# idro900ma.net
KiCad netlist of a schematic drawn in Altium Designer
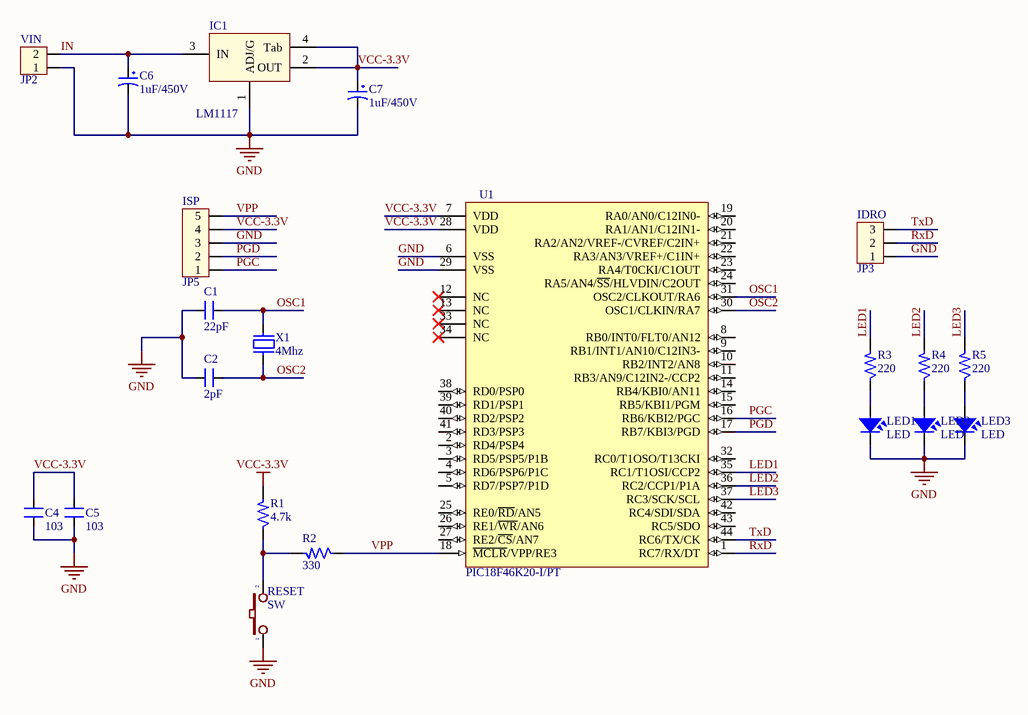
[diagram p0: idro900ma.SchDoc]

(export (version "E")
  (design (tool "Eeschema 10.0.6"))
  (components
    (comp (ref "C1")
      (value "22pF")
      (footprint "SM-0805")
      (description "Cap SMD")
      (libsource (lib "syhaunguyen") (part "CM"))
    )
    (comp (ref "C2")
      (value "2pF")
      (footprint "SM-0805")
      (description "Cap SMD")
      (libsource (lib "syhaunguyen") (part "CM"))
    )
    (comp (ref "C4")
      (value "103")
      (footprint "SM-0805")
      (description "Cap SMD")
      (libsource (lib "syhaunguyen") (part "CM"))
    )
    (comp (ref "C5")
      (value "103")
      (footprint "SM-0805")
      (description "Cap SMD")
      (libsource (lib "syhaunguyen") (part "CM"))
    )
    (comp (ref "C6")
      (value "1uF/450V")
      (footprint "SM-0805")
      (description "Cap 4700uF/50V")
      (libsource (lib "syhaunguyen") (part "CP8"))
    )
    (comp (ref "C7")
      (value "1uF/450V")
      (footprint "SM-0805")
      (description "Cap 4700uF/50V")
      (libsource (lib "syhaunguyen") (part "CP8"))
    )
    (comp (ref "IC1")
      (value "LM1117")
      (footprint "SOT223-4N")
      (description "3v3")
      (libsource (lib "syhaunguyen") (part "LM1117"))
    )
    (comp (ref "IDRO")
      (value "JP3")
      (footprint "CON3")
      (description "Connector 3")
      (libsource (lib "syhaunguyen") (part "Con3"))
    )
    (comp (ref "ISP")
      (value "JP5")
      (footprint "CON5")
      (description "Connector 5")
      (libsource (lib "syhaunguyen") (part "Con5"))
    )
    (comp (ref "LED1")
      (value "LED")
      (footprint "LED-5 GRe")
      (description "LED Single colour Green and Red")
      (libsource (lib "syhaunguyen") (part "LED"))
    )
    (comp (ref "LED2")
      (value "LED")
      (footprint "LED-5 GRe")
      (description "LED Single colour Green and Red")
      (libsource (lib "syhaunguyen") (part "LED"))
    )
    (comp (ref "LED3")
      (value "LED")
      (footprint "LED-5 GRe")
      (description "LED Single colour Green and Red")
      (libsource (lib "syhaunguyen") (part "LED"))
    )
    (comp (ref "R1")
      (value "4.7k")
      (footprint "SM-0805")
      (description "Resistor 1/4W")
      (libsource (lib "syhaunguyen") (part "R"))
    )
    (comp (ref "R2")
      (value "330")
      (footprint "SM-0805")
      (description "Resistor 1/4W")
      (libsource (lib "syhaunguyen") (part "R"))
    )
    (comp (ref "R3")
      (value "220")
      (footprint "SM-0805")
      (description "Resistor 1/4W")
      (libsource (lib "syhaunguyen") (part "R"))
    )
    (comp (ref "R4")
      (value "220")
      (footprint "SM-0805")
      (description "Resistor 1/4W")
      (libsource (lib "syhaunguyen") (part "R"))
    )
    (comp (ref "R5")
      (value "220")
      (footprint "SM-0805")
      (description "Resistor 1/4W")
      (libsource (lib "syhaunguyen") (part "R"))
    )
    (comp (ref "RESET")
      (value "SW")
      (footprint "SW2")
      (description "Switch button 2 pin")
      (libsource (lib "syhaunguyen") (part "SW2"))
    )
    (comp (ref "U1")
      (value "PIC18F46K20-I/PT")
      (footprint "TQFP-PT44_N")
      (fields (field (name "PUBLISHER") "Altium Limited"))
      (libsource (lib "Microchip Microcontroller 8-Bit PIC18") (part "PIC18F46K20-I/PT"))
    )
    (comp (ref "VIN")
      (value "JP2")
      (footprint "CON2")
      (description "Connector 2")
      (libsource (lib "syhaunguyen") (part "Con2"))
    )
    (comp (ref "X1")
      (value "4Mhz")
      (footprint "XT2")
      (description "Crystal For all Crystal 2pin.")
      (libsource (lib "syhaunguyen") (part "XT2"))
    )
  )
  (nets
    (net (code "1") (name "/IN") (class "Default")
      (node (ref "C6") (pin "1") (pinfunction "1_1") (pintype "passive"))
      (node (ref "IC1") (pin "3") (pinfunction "IN_3") (pintype "passive"))
      (node (ref "VIN") (pin "2") (pinfunction "2_2") (pintype "passive"))
    )
    (net (code "2") (name "/LED1") (class "Default")
      (node (ref "R3") (pin "2") (pinfunction "2_2") (pintype "passive"))
      (node (ref "U1") (pin "35") (pinfunction "RC1/T1OSI/CCP2_35") (pintype "bidirectional"))
    )
    (net (code "3") (name "/LED2") (class "Default")
      (node (ref "R4") (pin "2") (pinfunction "2_2") (pintype "passive"))
      (node (ref "U1") (pin "36") (pinfunction "RC2/CCP1/P1A_36") (pintype "bidirectional"))
    )
    (net (code "4") (name "/LED3") (class "Default")
      (node (ref "R5") (pin "2") (pinfunction "2_2") (pintype "passive"))
      (node (ref "U1") (pin "37") (pinfunction "RC3/SCK/SCL_37") (pintype "bidirectional"))
    )
    (net (code "5") (name "/OSC1") (class "Default")
      (node (ref "C1") (pin "2") (pinfunction "2_2") (pintype "passive"))
      (node (ref "U1") (pin "31") (pinfunction "OSC2/CLKOUT/RA6_31") (pintype "bidirectional"))
      (node (ref "X1") (pin "2") (pinfunction "2_2") (pintype "passive"))
    )
    (net (code "6") (name "/OSC2") (class "Default")
      (node (ref "C2") (pin "2") (pinfunction "2_2") (pintype "passive"))
      (node (ref "U1") (pin "30") (pinfunction "OSC1/CLKIN/RA7_30") (pintype "bidirectional"))
      (node (ref "X1") (pin "1") (pinfunction "1_1") (pintype "passive"))
    )
    (net (code "7") (name "/PGC") (class "Default")
      (node (ref "ISP") (pin "1") (pinfunction "1_1") (pintype "passive"))
      (node (ref "U1") (pin "16") (pinfunction "RB6/KBI2/PGC_16") (pintype "bidirectional"))
    )
    (net (code "8") (name "/PGD") (class "Default")
      (node (ref "ISP") (pin "2") (pinfunction "2_2") (pintype "passive"))
      (node (ref "U1") (pin "17") (pinfunction "RB7/KBI3/PGD_17") (pintype "bidirectional"))
    )
    (net (code "9") (name "/RxD") (class "Default")
      (node (ref "IDRO") (pin "2") (pinfunction "2_2") (pintype "passive"))
      (node (ref "U1") (pin "1") (pinfunction "RC7/RX/DT_1") (pintype "bidirectional"))
    )
    (net (code "10") (name "/TxD") (class "Default")
      (node (ref "IDRO") (pin "3") (pinfunction "3_3") (pintype "passive"))
      (node (ref "U1") (pin "44") (pinfunction "RC6/TX/CK_44") (pintype "bidirectional"))
    )
    (net (code "11") (name "/VPP") (class "Default")
      (node (ref "ISP") (pin "5") (pinfunction "5_5") (pintype "passive"))
      (node (ref "R2") (pin "1") (pinfunction "1_1") (pintype "passive"))
      (node (ref "U1") (pin "18") (pinfunction "~{MCLR}/VPP/RE3_18") (pintype "input"))
    )
    (net (code "12") (name "GND") (class "Default")
      (node (ref "C1") (pin "1") (pinfunction "1_1") (pintype "passive"))
      (node (ref "C2") (pin "1") (pinfunction "1_1") (pintype "passive"))
      (node (ref "C4") (pin "1") (pinfunction "1_1") (pintype "passive"))
      (node (ref "C5") (pin "1") (pinfunction "1_1") (pintype "passive"))
      (node (ref "C6") (pin "2") (pinfunction "2_2") (pintype "passive"))
      (node (ref "C7") (pin "2") (pinfunction "2_2") (pintype "passive"))
      (node (ref "IC1") (pin "1") (pinfunction "ADJ/G_1") (pintype "passive"))
      (node (ref "IDRO") (pin "1") (pinfunction "1_1") (pintype "passive"))
      (node (ref "ISP") (pin "3") (pinfunction "3_3") (pintype "passive"))
      (node (ref "LED1") (pin "2") (pinfunction "2_2") (pintype "passive"))
      (node (ref "LED2") (pin "2") (pinfunction "2_2") (pintype "passive"))
      (node (ref "LED3") (pin "2") (pinfunction "2_2") (pintype "passive"))
      (node (ref "RESET") (pin "1") (pinfunction "1_1") (pintype "passive"))
      (node (ref "U1") (pin "29") (pinfunction "VSS_29") (pintype "power_in"))
      (node (ref "U1") (pin "6") (pinfunction "VSS_6") (pintype "power_in"))
      (node (ref "VIN") (pin "1") (pinfunction "1_1") (pintype "passive"))
    )
    (net (code "13") (name "Net-(LED1-Pad1)") (class "Default")
      (node (ref "LED1") (pin "1") (pinfunction "1_1") (pintype "passive"))
      (node (ref "R3") (pin "1") (pinfunction "1_1") (pintype "passive"))
    )
    (net (code "14") (name "Net-(LED2-Pad1)") (class "Default")
      (node (ref "LED2") (pin "1") (pinfunction "1_1") (pintype "passive"))
      (node (ref "R4") (pin "1") (pinfunction "1_1") (pintype "passive"))
    )
    (net (code "15") (name "Net-(LED3-Pad1)") (class "Default")
      (node (ref "LED3") (pin "1") (pinfunction "1_1") (pintype "passive"))
      (node (ref "R5") (pin "1") (pinfunction "1_1") (pintype "passive"))
    )
    (net (code "16") (name "Net-(R1-Pad1)") (class "Default")
      (node (ref "R1") (pin "1") (pinfunction "1_1") (pintype "passive"))
      (node (ref "R2") (pin "2") (pinfunction "2_2") (pintype "passive"))
      (node (ref "RESET") (pin "2") (pinfunction "2_2") (pintype "passive"))
    )
    (net (code "17") (name "VCC-3.3V") (class "Default")
      (node (ref "C4") (pin "2") (pinfunction "2_2") (pintype "passive"))
      (node (ref "C5") (pin "2") (pinfunction "2_2") (pintype "passive"))
      (node (ref "C7") (pin "1") (pinfunction "1_1") (pintype "passive"))
      (node (ref "IC1") (pin "2") (pinfunction "OUT_2") (pintype "passive"))
      (node (ref "IC1") (pin "4") (pinfunction "Tab_4") (pintype "passive"))
      (node (ref "ISP") (pin "4") (pinfunction "4_4") (pintype "passive"))
      (node (ref "R1") (pin "2") (pinfunction "2_2") (pintype "passive"))
      (node (ref "U1") (pin "28") (pinfunction "VDD_28") (pintype "power_in"))
      (node (ref "U1") (pin "7") (pinfunction "VDD_7") (pintype "power_in"))
    )
    (net (code "18") (name "unconnected-(U1-NC-Pad12)") (class "Default")
      (node (ref "U1") (pin "12") (pinfunction "NC_12") (pintype "passive+no_connect"))
    )
    (net (code "19") (name "unconnected-(U1-NC-Pad13)") (class "Default")
      (node (ref "U1") (pin "13") (pinfunction "NC_13") (pintype "passive+no_connect"))
    )
    (net (code "20") (name "unconnected-(U1-NC-Pad33)") (class "Default")
      (node (ref "U1") (pin "33") (pinfunction "NC_33") (pintype "passive+no_connect"))
    )
    (net (code "21") (name "unconnected-(U1-NC-Pad34)") (class "Default")
      (node (ref "U1") (pin "34") (pinfunction "NC_34") (pintype "passive+no_connect"))
    )
    (net (code "22") (name "unconnected-(U1-RA0{slash}AN0{slash}C12IN0--Pad19)") (class "Default")
      (node (ref "U1") (pin "19") (pinfunction "RA0/AN0/C12IN0-_19") (pintype "bidirectional"))
    )
    (net (code "23") (name "unconnected-(U1-RA1{slash}AN1{slash}C12IN1--Pad20)") (class "Default")
      (node (ref "U1") (pin "20") (pinfunction "RA1/AN1/C12IN1-_20") (pintype "bidirectional"))
    )
    (net (code "24") (name "unconnected-(U1-RA2{slash}AN2{slash}VREF-{slash}CVREF{slash}C2IN+-Pad21)") (class "Default")
      (node (ref "U1") (pin "21") (pinfunction "RA2/AN2/VREF-/CVREF/C2IN+_21") (pintype "bidirectional"))
    )
    (net (code "25") (name "unconnected-(U1-RA3{slash}AN3{slash}VREF+{slash}C1IN+-Pad22)") (class "Default")
      (node (ref "U1") (pin "22") (pinfunction "RA3/AN3/VREF+/C1IN+_22") (pintype "bidirectional"))
    )
    (net (code "26") (name "unconnected-(U1-RA4{slash}T0CKI{slash}C1OUT-Pad23)") (class "Default")
      (node (ref "U1") (pin "23") (pinfunction "RA4/T0CKI/C1OUT_23") (pintype "bidirectional"))
    )
    (net (code "27") (name "unconnected-(U1-RA5{slash}AN4{slash}~{SS}{slash}HLVDIN{slash}C2OUT-Pad24)") (class "Default")
      (node (ref "U1") (pin "24") (pinfunction "RA5/AN4/~{SS}/HLVDIN/C2OUT_24") (pintype "bidirectional"))
    )
    (net (code "28") (name "unconnected-(U1-RB0{slash}INT0{slash}FLT0{slash}AN12-Pad8)") (class "Default")
      (node (ref "U1") (pin "8") (pinfunction "RB0/INT0/FLT0/AN12_8") (pintype "bidirectional"))
    )
    (net (code "29") (name "unconnected-(U1-RB1{slash}INT1{slash}AN10{slash}C12IN3--Pad9)") (class "Default")
      (node (ref "U1") (pin "9") (pinfunction "RB1/INT1/AN10/C12IN3-_9") (pintype "bidirectional"))
    )
    (net (code "30") (name "unconnected-(U1-RB2{slash}INT2{slash}AN8-Pad10)") (class "Default")
      (node (ref "U1") (pin "10") (pinfunction "RB2/INT2/AN8_10") (pintype "bidirectional"))
    )
    (net (code "31") (name "unconnected-(U1-RB3{slash}AN9{slash}C12IN2-{slash}CCP2-Pad11)") (class "Default")
      (node (ref "U1") (pin "11") (pinfunction "RB3/AN9/C12IN2-/CCP2_11") (pintype "bidirectional"))
    )
    (net (code "32") (name "unconnected-(U1-RB4{slash}KBI0{slash}AN11-Pad14)") (class "Default")
      (node (ref "U1") (pin "14") (pinfunction "RB4/KBI0/AN11_14") (pintype "bidirectional"))
    )
    (net (code "33") (name "unconnected-(U1-RB5{slash}KBI1{slash}PGM-Pad15)") (class "Default")
      (node (ref "U1") (pin "15") (pinfunction "RB5/KBI1/PGM_15") (pintype "bidirectional"))
    )
    (net (code "34") (name "unconnected-(U1-RC0{slash}T1OSO{slash}T13CKI-Pad32)") (class "Default")
      (node (ref "U1") (pin "32") (pinfunction "RC0/T1OSO/T13CKI_32") (pintype "bidirectional"))
    )
    (net (code "35") (name "unconnected-(U1-RC4{slash}SDI{slash}SDA-Pad42)") (class "Default")
      (node (ref "U1") (pin "42") (pinfunction "RC4/SDI/SDA_42") (pintype "bidirectional"))
    )
    (net (code "36") (name "unconnected-(U1-RC5{slash}SDO-Pad43)") (class "Default")
      (node (ref "U1") (pin "43") (pinfunction "RC5/SDO_43") (pintype "bidirectional"))
    )
    (net (code "37") (name "unconnected-(U1-RD0{slash}PSP0-Pad38)") (class "Default")
      (node (ref "U1") (pin "38") (pinfunction "RD0/PSP0_38") (pintype "bidirectional"))
    )
    (net (code "38") (name "unconnected-(U1-RD1{slash}PSP1-Pad39)") (class "Default")
      (node (ref "U1") (pin "39") (pinfunction "RD1/PSP1_39") (pintype "bidirectional"))
    )
    (net (code "39") (name "unconnected-(U1-RD2{slash}PSP2-Pad40)") (class "Default")
      (node (ref "U1") (pin "40") (pinfunction "RD2/PSP2_40") (pintype "bidirectional"))
    )
    (net (code "40") (name "unconnected-(U1-RD3{slash}PSP3-Pad41)") (class "Default")
      (node (ref "U1") (pin "41") (pinfunction "RD3/PSP3_41") (pintype "bidirectional"))
    )
    (net (code "41") (name "unconnected-(U1-RD4{slash}PSP4-Pad2)") (class "Default")
      (node (ref "U1") (pin "2") (pinfunction "RD4/PSP4_2") (pintype "bidirectional"))
    )
    (net (code "42") (name "unconnected-(U1-RD5{slash}PSP5{slash}P1B-Pad3)") (class "Default")
      (node (ref "U1") (pin "3") (pinfunction "RD5/PSP5/P1B_3") (pintype "bidirectional"))
    )
    (net (code "43") (name "unconnected-(U1-RD6{slash}PSP6{slash}P1C-Pad4)") (class "Default")
      (node (ref "U1") (pin "4") (pinfunction "RD6/PSP6/P1C_4") (pintype "bidirectional"))
    )
    (net (code "44") (name "unconnected-(U1-RD7{slash}PSP7{slash}P1D-Pad5)") (class "Default")
      (node (ref "U1") (pin "5") (pinfunction "RD7/PSP7/P1D_5") (pintype "bidirectional"))
    )
    (net (code "45") (name "unconnected-(U1-RE0{slash}~{RD}{slash}AN5-Pad25)") (class "Default")
      (node (ref "U1") (pin "25") (pinfunction "RE0/~{RD}/AN5_25") (pintype "bidirectional"))
    )
    (net (code "46") (name "unconnected-(U1-RE1{slash}~{WR}{slash}AN6-Pad26)") (class "Default")
      (node (ref "U1") (pin "26") (pinfunction "RE1/~{WR}/AN6_26") (pintype "bidirectional"))
    )
    (net (code "47") (name "unconnected-(U1-RE2{slash}~{CS}{slash}AN7-Pad27)") (class "Default")
      (node (ref "U1") (pin "27") (pinfunction "RE2/~{CS}/AN7_27") (pintype "bidirectional"))
    )
  )
)
